# Onboard_LEDs.net
KiCad netlist of a schematic drawn in Altium Designer
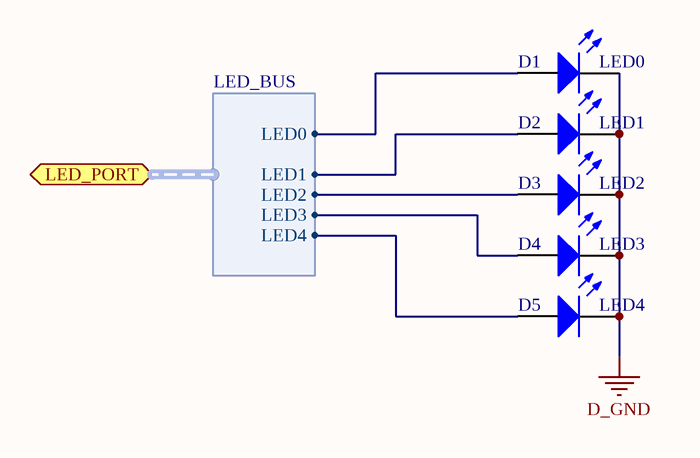
[diagram p0: Onboard_LEDs.SchDoc]

(export (version "E")
  (design (tool "Eeschema 10.0.6"))
  (components
    (comp (ref "D1")
      (value "LED0")
      (footprint "LEDCP1006X02N_PICOLED_0402:LEDCP1006X02N")
      (description "Typical INFRARED GaAs LED")
      (fields (field (name "PUBLISHER") "Altium Limited"))
      (libsource (lib "Miscellaneous Devices") (part "LED0"))
    )
    (comp (ref "D2")
      (value "LED1")
      (footprint "LEDCP1006X02N_PICOLED_0402:LEDCP1006X02N")
      (description "Typical INFRARED GaAs LED")
      (fields (field (name "PUBLISHER") "Altium Limited"))
      (libsource (lib "Miscellaneous Devices") (part "LED0"))
    )
    (comp (ref "D3")
      (value "LED2")
      (footprint "LEDCP1006X02N_PICOLED_0402:LEDCP1006X02N")
      (description "Typical INFRARED GaAs LED")
      (fields (field (name "PUBLISHER") "Altium Limited"))
      (libsource (lib "Miscellaneous Devices") (part "LED0"))
    )
    (comp (ref "D4")
      (value "LED3")
      (footprint "LEDCP1006X02N_PICOLED_0402:LEDCP1006X02N")
      (description "Typical INFRARED GaAs LED")
      (fields (field (name "PUBLISHER") "Altium Limited"))
      (libsource (lib "Miscellaneous Devices") (part "LED0"))
    )
    (comp (ref "D5")
      (value "LED4")
      (footprint "LEDCP1006X02N_PICOLED_0402:LEDCP1006X02N")
      (description "Typical INFRARED GaAs LED")
      (fields (field (name "PUBLISHER") "Altium Limited"))
      (libsource (lib "Miscellaneous Devices") (part "LED0"))
    )
  )
  (nets
    (net (code "2") (name "/LED0") (class "Default")
      (node (ref "D1") (pin "1") (pinfunction "A_1") (pintype "passive"))
    )
    (net (code "3") (name "/LED1") (class "Default")
      (node (ref "D2") (pin "1") (pinfunction "A_1") (pintype "passive"))
    )
    (net (code "4") (name "/LED2") (class "Default")
      (node (ref "D3") (pin "1") (pinfunction "A_1") (pintype "passive"))
    )
    (net (code "5") (name "/LED3") (class "Default")
      (node (ref "D4") (pin "1") (pinfunction "A_1") (pintype "passive"))
    )
    (net (code "6") (name "/LED4") (class "Default")
      (node (ref "D5") (pin "1") (pinfunction "A_1") (pintype "passive"))
    )
    (net (code "8") (name "D_GND") (class "Default")
      (node (ref "D1") (pin "2") (pinfunction "K_2") (pintype "passive"))
      (node (ref "D2") (pin "2") (pinfunction "K_2") (pintype "passive"))
      (node (ref "D3") (pin "2") (pinfunction "K_2") (pintype "passive"))
      (node (ref "D4") (pin "2") (pinfunction "K_2") (pintype "passive"))
      (node (ref "D5") (pin "2") (pinfunction "K_2") (pintype "passive"))
    )
  )
)
